# Minimum-System.net
KiCad netlist of a schematic drawn in EAGLE
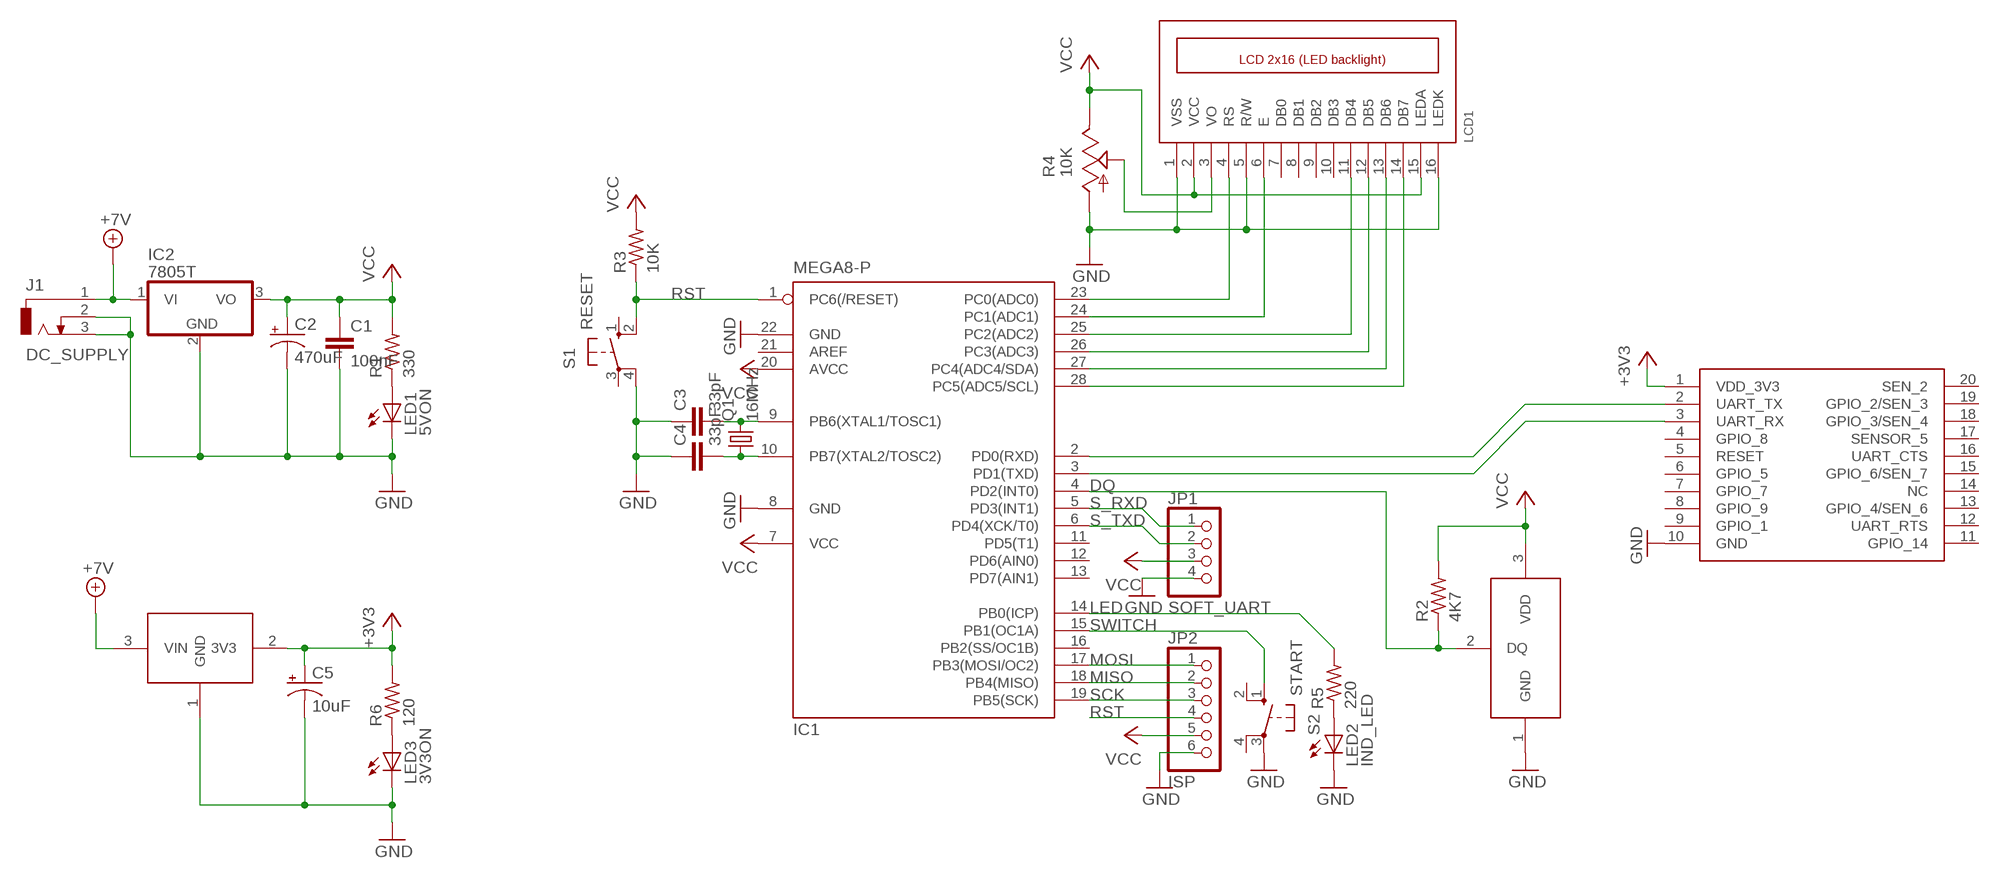
[diagram p0: schematic, sheet 1]

(export (version "E")
  (design (tool "Eeschema 10.0.6"))
  (components
    (comp (ref "C1")
      (value "100nF")
      (footprint "eagle-import:C025-024X044")
      (libsource (lib "eagle-import") (part "C-EU025-024X044"))
    )
    (comp (ref "C2")
      (value "470uF")
      (footprint "eagle-import:E2,5-7")
      (libsource (lib "eagle-import") (part "CPOL-USE2.5-7"))
    )
    (comp (ref "C3")
      (value "33pF")
      (footprint "eagle-import:C025-024X044")
      (libsource (lib "eagle-import") (part "C-EU025-024X044"))
    )
    (comp (ref "C4")
      (value "33pF")
      (footprint "eagle-import:C025-024X044")
      (libsource (lib "eagle-import") (part "C-EU025-024X044"))
    )
    (comp (ref "C5")
      (value "10uF")
      (footprint "eagle-import:E2,5-7")
      (libsource (lib "eagle-import") (part "CPOL-USE2.5-7"))
    )
    (comp (ref "IC1")
      (value "MEGA8-P")
      (footprint "eagle-import:DIL28-3")
      (libsource (lib "eagle-import") (part "MEGA8-P"))
    )
    (comp (ref "IC2")
      (value "7805T")
      (footprint "eagle-import:TO220H")
      (libsource (lib "eagle-import") (part "78T05"))
    )
    (comp (ref "J1")
      (value "DC_SUPPLY")
      (footprint "eagle-import:DCJ0202")
      (libsource (lib "eagle-import") (part "DCJ0202"))
    )
    (comp (ref "JP1")
      (value "SOFT_UART")
      (footprint "eagle-import:1X04")
      (libsource (lib "eagle-import") (part "PINHD-1X4"))
    )
    (comp (ref "JP2")
      (value "ISP")
      (footprint "eagle-import:1X06")
      (libsource (lib "eagle-import") (part "PINHD-1X6"))
    )
    (comp (ref "LCD1")
      (value "LCD_2X16")
      (footprint "eagle-import:HY-1602F")
      (libsource (lib "eagle-import") (part "LCD_2X16_SIL"))
    )
    (comp (ref "LED1")
      (value "5VON")
      (footprint "eagle-import:LED3MM")
      (libsource (lib "eagle-import") (part "LED3MM"))
    )
    (comp (ref "LED2")
      (value "IND_LED")
      (footprint "eagle-import:LED3MM")
      (libsource (lib "eagle-import") (part "LED3MM"))
    )
    (comp (ref "LED3")
      (value "3V3ON")
      (footprint "eagle-import:LED3MM")
      (libsource (lib "eagle-import") (part "LED3MM"))
    )
    (comp (ref "Q1")
      (value "16MHz")
      (footprint "eagle-import:HC49_S")
      (libsource (lib "eagle-import") (part "CRYSTALHC49S"))
    )
    (comp (ref "R1")
      (value "330")
      (footprint "eagle-import:0207_10")
      (libsource (lib "eagle-import") (part "R-US_0207/10"))
    )
    (comp (ref "R2")
      (value "4K7")
      (footprint "eagle-import:0207_10")
      (libsource (lib "eagle-import") (part "R-US_0207/10"))
    )
    (comp (ref "R3")
      (value "10K")
      (footprint "eagle-import:0207_10")
      (libsource (lib "eagle-import") (part "R-US_0207/10"))
    )
    (comp (ref "R4")
      (value "10K")
      (footprint "eagle-import:CA6V")
      (libsource (lib "eagle-import") (part "TRIM_US-CA6V"))
    )
    (comp (ref "R5")
      (value "220")
      (footprint "eagle-import:0207_10")
      (libsource (lib "eagle-import") (part "R-US_0207/10"))
    )
    (comp (ref "R6")
      (value "120")
      (footprint "eagle-import:0207_10")
      (libsource (lib "eagle-import") (part "R-US_0207/10"))
    )
    (comp (ref "S1")
      (value "RESET")
      (footprint "eagle-import:B3F-10XX")
      (fields (field (name "MPN") "B3F-1000"))
      (libsource (lib "eagle-import") (part "10-XX"))
    )
    (comp (ref "S2")
      (value "START")
      (footprint "eagle-import:B3F-10XX")
      (fields (field (name "MPN") "B3F-1000"))
      (libsource (lib "eagle-import") (part "10-XX"))
    )
    (comp (ref "U1")
      (value "DS1820")
      (footprint "eagle-import:TO92")
      (libsource (lib "eagle-import") (part "DS1820"))
    )
    (comp (ref "U2")
      (value "LD1117V33")
      (footprint "eagle-import:TO220")
      (libsource (lib "eagle-import") (part "LD1117V33"))
    )
    (comp (ref "U3")
      (value "WIFLY")
      (footprint "eagle-import:WIFLY_SOCKET")
      (libsource (lib "eagle-import") (part "WIFLY"))
    )
  )
  (nets
    (net (code "1") (name "+3V3") (class "Default")
      (node (ref "C5") (pin "+") (pinfunction "+_+") (pintype "passive"))
      (node (ref "R6") (pin "2") (pinfunction "2_2") (pintype "passive"))
      (node (ref "U2") (pin "2") (pinfunction "3V3_2") (pintype "bidirectional"))
      (node (ref "U3") (pin "1") (pinfunction "VDD_3V3_1") (pintype "power_in"))
    )
    (net (code "2") (name "+7V") (class "Default")
      (node (ref "IC2") (pin "1") (pinfunction "VI_1") (pintype "input"))
      (node (ref "J1") (pin "1") (pinfunction "1_1") (pintype "passive"))
      (node (ref "U2") (pin "3") (pinfunction "VIN_3") (pintype "input"))
    )
    (net (code "3") (name "/DQ") (class "Default")
      (node (ref "IC1") (pin "4") (pinfunction "PD2(INT0)_4") (pintype "bidirectional"))
      (node (ref "R2") (pin "1") (pinfunction "1_1") (pintype "passive"))
      (node (ref "U1") (pin "2") (pinfunction "DQ_2") (pintype "bidirectional"))
    )
    (net (code "4") (name "/LED") (class "Default")
      (node (ref "IC1") (pin "14") (pinfunction "PB0(ICP)_14") (pintype "bidirectional"))
      (node (ref "R5") (pin "2") (pinfunction "2_2") (pintype "passive"))
    )
    (net (code "5") (name "/MISO") (class "Default")
      (node (ref "IC1") (pin "18") (pinfunction "PB4(MISO)_18") (pintype "bidirectional"))
      (node (ref "JP2") (pin "2") (pinfunction "2_2") (pintype "passive"))
    )
    (net (code "6") (name "/MOSI") (class "Default")
      (node (ref "IC1") (pin "17") (pinfunction "PB3(MOSI/OC2)_17") (pintype "bidirectional"))
      (node (ref "JP2") (pin "1") (pinfunction "1_1") (pintype "passive"))
    )
    (net (code "7") (name "/RST") (class "Default")
      (node (ref "IC1") (pin "1") (pinfunction "PC6(/RESET)_1") (pintype "bidirectional"))
      (node (ref "JP2") (pin "4") (pinfunction "4_4") (pintype "passive"))
      (node (ref "R3") (pin "1") (pinfunction "1_1") (pintype "passive"))
      (node (ref "S1") (pin "2") (pinfunction "S1_2") (pintype "passive"))
    )
    (net (code "8") (name "/SCK") (class "Default")
      (node (ref "IC1") (pin "19") (pinfunction "PB5(SCK)_19") (pintype "bidirectional"))
      (node (ref "JP2") (pin "3") (pinfunction "3_3") (pintype "passive"))
    )
    (net (code "9") (name "/SWITCH") (class "Default")
      (node (ref "IC1") (pin "15") (pinfunction "PB1(OC1A)_15") (pintype "bidirectional"))
      (node (ref "S2") (pin "1") (pinfunction "S_1") (pintype "passive"))
    )
    (net (code "10") (name "/S_RXD") (class "Default")
      (node (ref "IC1") (pin "5") (pinfunction "PD3(INT1)_5") (pintype "bidirectional"))
      (node (ref "JP1") (pin "1") (pinfunction "1_1") (pintype "passive"))
    )
    (net (code "11") (name "/S_TXD") (class "Default")
      (node (ref "IC1") (pin "6") (pinfunction "PD4(XCK/T0)_6") (pintype "bidirectional"))
      (node (ref "JP1") (pin "2") (pinfunction "2_2") (pintype "passive"))
    )
    (net (code "12") (name "GND") (class "Default")
      (node (ref "C1") (pin "2") (pinfunction "2_2") (pintype "passive"))
      (node (ref "C2") (pin "-") (pinfunction "-_-") (pintype "passive"))
      (node (ref "C3") (pin "1") (pinfunction "1_1") (pintype "passive"))
      (node (ref "C4") (pin "1") (pinfunction "1_1") (pintype "passive"))
      (node (ref "C5") (pin "-") (pinfunction "-_-") (pintype "passive"))
      (node (ref "IC1") (pin "22") (pinfunction "GND_22") (pintype "power_in"))
      (node (ref "IC1") (pin "8") (pinfunction "GND_8") (pintype "power_in"))
      (node (ref "IC2") (pin "2") (pinfunction "GND_2") (pintype "passive"))
      (node (ref "J1") (pin "2") (pinfunction "2_2") (pintype "passive"))
      (node (ref "J1") (pin "3") (pinfunction "3_3") (pintype "passive"))
      (node (ref "JP1") (pin "4") (pinfunction "4_4") (pintype "passive"))
      (node (ref "JP2") (pin "6") (pinfunction "6_6") (pintype "passive"))
      (node (ref "LCD1") (pin "1") (pinfunction "VSS_1") (pintype "power_in"))
      (node (ref "LCD1") (pin "16") (pinfunction "LEDK_16") (pintype "passive"))
      (node (ref "LCD1") (pin "5") (pinfunction "R/W_5") (pintype "input"))
      (node (ref "LED1") (pin "K") (pinfunction "C_K") (pintype "passive"))
      (node (ref "LED2") (pin "K") (pinfunction "C_K") (pintype "passive"))
      (node (ref "LED3") (pin "K") (pinfunction "C_K") (pintype "passive"))
      (node (ref "R4") (pin "A") (pinfunction "A_A") (pintype "passive"))
      (node (ref "S1") (pin "4") (pinfunction "P1_4") (pintype "passive"))
      (node (ref "S2") (pin "3") (pinfunction "P_3") (pintype "passive"))
      (node (ref "U1") (pin "1") (pinfunction "GND_1") (pintype "power_in"))
      (node (ref "U2") (pin "1") (pinfunction "GND_1") (pintype "power_in"))
      (node (ref "U3") (pin "10") (pinfunction "GND_10") (pintype "power_in"))
    )
    (net (code "13") (name "Net-(IC1-PB6(XTAL1{slash}TOSC1))") (class "Default")
      (node (ref "C3") (pin "2") (pinfunction "2_2") (pintype "passive"))
      (node (ref "IC1") (pin "9") (pinfunction "PB6(XTAL1/TOSC1)_9") (pintype "bidirectional"))
      (node (ref "Q1") (pin "2") (pinfunction "2_2") (pintype "passive"))
    )
    (net (code "14") (name "Net-(IC1-PB7(XTAL2{slash}TOSC2))") (class "Default")
      (node (ref "C4") (pin "2") (pinfunction "2_2") (pintype "passive"))
      (node (ref "IC1") (pin "10") (pinfunction "PB7(XTAL2/TOSC2)_10") (pintype "bidirectional"))
      (node (ref "Q1") (pin "1") (pinfunction "1_1") (pintype "passive"))
    )
    (net (code "15") (name "Net-(IC1-PC0(ADC0))") (class "Default")
      (node (ref "IC1") (pin "23") (pinfunction "PC0(ADC0)_23") (pintype "bidirectional"))
      (node (ref "LCD1") (pin "4") (pinfunction "RS_4") (pintype "input"))
    )
    (net (code "16") (name "Net-(IC1-PC1(ADC1))") (class "Default")
      (node (ref "IC1") (pin "24") (pinfunction "PC1(ADC1)_24") (pintype "bidirectional"))
      (node (ref "LCD1") (pin "6") (pinfunction "E_6") (pintype "input"))
    )
    (net (code "17") (name "Net-(IC1-PC2(ADC2))") (class "Default")
      (node (ref "IC1") (pin "25") (pinfunction "PC2(ADC2)_25") (pintype "bidirectional"))
      (node (ref "LCD1") (pin "11") (pinfunction "DB4_11") (pintype "bidirectional"))
    )
    (net (code "18") (name "Net-(IC1-PC3(ADC3))") (class "Default")
      (node (ref "IC1") (pin "26") (pinfunction "PC3(ADC3)_26") (pintype "bidirectional"))
      (node (ref "LCD1") (pin "12") (pinfunction "DB5_12") (pintype "bidirectional"))
    )
    (net (code "19") (name "Net-(IC1-PC4(ADC4{slash}SDA))") (class "Default")
      (node (ref "IC1") (pin "27") (pinfunction "PC4(ADC4/SDA)_27") (pintype "bidirectional"))
      (node (ref "LCD1") (pin "13") (pinfunction "DB6_13") (pintype "bidirectional"))
    )
    (net (code "20") (name "Net-(IC1-PC5(ADC5{slash}SCL))") (class "Default")
      (node (ref "IC1") (pin "28") (pinfunction "PC5(ADC5/SCL)_28") (pintype "bidirectional"))
      (node (ref "LCD1") (pin "14") (pinfunction "DB7_14") (pintype "bidirectional"))
    )
    (net (code "21") (name "Net-(IC1-PD0(RXD))") (class "Default")
      (node (ref "IC1") (pin "2") (pinfunction "PD0(RXD)_2") (pintype "bidirectional"))
      (node (ref "U3") (pin "2") (pinfunction "UART_TX_2") (pintype "bidirectional"))
    )
    (net (code "22") (name "Net-(IC1-PD1(TXD))") (class "Default")
      (node (ref "IC1") (pin "3") (pinfunction "PD1(TXD)_3") (pintype "bidirectional"))
      (node (ref "U3") (pin "3") (pinfunction "UART_RX_3") (pintype "bidirectional"))
    )
    (net (code "23") (name "Net-(LCD1-VO)") (class "Default")
      (node (ref "LCD1") (pin "3") (pinfunction "VO_3") (pintype "input"))
      (node (ref "R4") (pin "S") (pinfunction "S_S") (pintype "passive"))
    )
    (net (code "24") (name "Net-(LED1-PadA)") (class "Default")
      (node (ref "LED1") (pin "A") (pinfunction "A_A") (pintype "passive"))
      (node (ref "R1") (pin "1") (pinfunction "1_1") (pintype "passive"))
    )
    (net (code "25") (name "Net-(LED2-PadA)") (class "Default")
      (node (ref "LED2") (pin "A") (pinfunction "A_A") (pintype "passive"))
      (node (ref "R5") (pin "1") (pinfunction "1_1") (pintype "passive"))
    )
    (net (code "26") (name "Net-(LED3-PadA)") (class "Default")
      (node (ref "LED3") (pin "A") (pinfunction "A_A") (pintype "passive"))
      (node (ref "R6") (pin "1") (pinfunction "1_1") (pintype "passive"))
    )
    (net (code "27") (name "VCC") (class "Default")
      (node (ref "C1") (pin "1") (pinfunction "1_1") (pintype "passive"))
      (node (ref "C2") (pin "+") (pinfunction "+_+") (pintype "passive"))
      (node (ref "IC1") (pin "20") (pinfunction "AVCC_20") (pintype "power_in"))
      (node (ref "IC1") (pin "7") (pinfunction "VCC_7") (pintype "power_in"))
      (node (ref "IC2") (pin "3") (pinfunction "VO_3") (pintype "passive"))
      (node (ref "JP1") (pin "3") (pinfunction "3_3") (pintype "passive"))
      (node (ref "JP2") (pin "5") (pinfunction "5_5") (pintype "passive"))
      (node (ref "LCD1") (pin "15") (pinfunction "LEDA_15") (pintype "passive"))
      (node (ref "LCD1") (pin "2") (pinfunction "VCC_2") (pintype "power_in"))
      (node (ref "R1") (pin "2") (pinfunction "2_2") (pintype "passive"))
      (node (ref "R2") (pin "2") (pinfunction "2_2") (pintype "passive"))
      (node (ref "R3") (pin "2") (pinfunction "2_2") (pintype "passive"))
      (node (ref "R4") (pin "E") (pinfunction "E_E") (pintype "passive"))
      (node (ref "U1") (pin "3") (pinfunction "VDD_3") (pintype "power_in"))
    )
    (net (code "28") (name "unconnected-(IC1-AREF-Pad21)") (class "Default")
      (node (ref "IC1") (pin "21") (pinfunction "AREF_21") (pintype "passive"))
    )
    (net (code "29") (name "unconnected-(IC1-PB2(SS{slash}OC1B)-Pad16)") (class "Default")
      (node (ref "IC1") (pin "16") (pinfunction "PB2(SS/OC1B)_16") (pintype "bidirectional"))
    )
    (net (code "30") (name "unconnected-(IC1-PD5(T1)-Pad11)") (class "Default")
      (node (ref "IC1") (pin "11") (pinfunction "PD5(T1)_11") (pintype "bidirectional"))
    )
    (net (code "31") (name "unconnected-(IC1-PD6(AIN0)-Pad12)") (class "Default")
      (node (ref "IC1") (pin "12") (pinfunction "PD6(AIN0)_12") (pintype "bidirectional"))
    )
    (net (code "32") (name "unconnected-(IC1-PD7(AIN1)-Pad13)") (class "Default")
      (node (ref "IC1") (pin "13") (pinfunction "PD7(AIN1)_13") (pintype "bidirectional"))
    )
    (net (code "33") (name "unconnected-(LCD1-DB0-Pad7)") (class "Default")
      (node (ref "LCD1") (pin "7") (pinfunction "DB0_7") (pintype "bidirectional"))
    )
    (net (code "34") (name "unconnected-(LCD1-DB1-Pad8)") (class "Default")
      (node (ref "LCD1") (pin "8") (pinfunction "DB1_8") (pintype "bidirectional"))
    )
    (net (code "35") (name "unconnected-(LCD1-DB2-Pad9)") (class "Default")
      (node (ref "LCD1") (pin "9") (pinfunction "DB2_9") (pintype "bidirectional"))
    )
    (net (code "36") (name "unconnected-(LCD1-DB3-Pad10)") (class "Default")
      (node (ref "LCD1") (pin "10") (pinfunction "DB3_10") (pintype "bidirectional"))
    )
    (net (code "37") (name "unconnected-(S1-P-Pad3)") (class "Default")
      (node (ref "S1") (pin "3") (pinfunction "P_3") (pintype "passive"))
    )
    (net (code "38") (name "unconnected-(S1-S-Pad1)") (class "Default")
      (node (ref "S1") (pin "1") (pinfunction "S_1") (pintype "passive"))
    )
    (net (code "39") (name "unconnected-(S2-P1-Pad4)") (class "Default")
      (node (ref "S2") (pin "4") (pinfunction "P1_4") (pintype "passive"))
    )
    (net (code "40") (name "unconnected-(S2-S1-Pad2)") (class "Default")
      (node (ref "S2") (pin "2") (pinfunction "S1_2") (pintype "passive"))
    )
    (net (code "41") (name "unconnected-(U3-GPIO_1-Pad9)") (class "Default")
      (node (ref "U3") (pin "9") (pinfunction "GPIO_1_9") (pintype "bidirectional"))
    )
    (net (code "42") (name "unconnected-(U3-GPIO_2{slash}SEN_3-Pad19)") (class "Default")
      (node (ref "U3") (pin "19") (pinfunction "GPIO_2/SEN_3_19") (pintype "bidirectional"))
    )
    (net (code "43") (name "unconnected-(U3-GPIO_3{slash}SEN_4-Pad18)") (class "Default")
      (node (ref "U3") (pin "18") (pinfunction "GPIO_3/SEN_4_18") (pintype "bidirectional"))
    )
    (net (code "44") (name "unconnected-(U3-GPIO_4{slash}SEN_6-Pad13)") (class "Default")
      (node (ref "U3") (pin "13") (pinfunction "GPIO_4/SEN_6_13") (pintype "bidirectional"))
    )
    (net (code "45") (name "unconnected-(U3-GPIO_5-Pad6)") (class "Default")
      (node (ref "U3") (pin "6") (pinfunction "GPIO_5_6") (pintype "bidirectional"))
    )
    (net (code "46") (name "unconnected-(U3-GPIO_6{slash}SEN_7-Pad15)") (class "Default")
      (node (ref "U3") (pin "15") (pinfunction "GPIO_6/SEN_7_15") (pintype "bidirectional"))
    )
    (net (code "47") (name "unconnected-(U3-GPIO_7-Pad7)") (class "Default")
      (node (ref "U3") (pin "7") (pinfunction "GPIO_7_7") (pintype "bidirectional"))
    )
    (net (code "48") (name "unconnected-(U3-GPIO_8-Pad4)") (class "Default")
      (node (ref "U3") (pin "4") (pinfunction "GPIO_8_4") (pintype "bidirectional"))
    )
    (net (code "49") (name "unconnected-(U3-GPIO_9-Pad8)") (class "Default")
      (node (ref "U3") (pin "8") (pinfunction "GPIO_9_8") (pintype "bidirectional"))
    )
    (net (code "50") (name "unconnected-(U3-GPIO_14-Pad11)") (class "Default")
      (node (ref "U3") (pin "11") (pinfunction "GPIO_14_11") (pintype "bidirectional"))
    )
    (net (code "51") (name "unconnected-(U3-NC-Pad14)") (class "Default")
      (node (ref "U3") (pin "14") (pinfunction "NC_14") (pintype "bidirectional"))
    )
    (net (code "52") (name "unconnected-(U3-RESET-Pad5)") (class "Default")
      (node (ref "U3") (pin "5") (pinfunction "RESET_5") (pintype "bidirectional"))
    )
    (net (code "53") (name "unconnected-(U3-SENSOR_5-Pad17)") (class "Default")
      (node (ref "U3") (pin "17") (pinfunction "SENSOR_5_17") (pintype "bidirectional"))
    )
    (net (code "54") (name "unconnected-(U3-SEN_2-Pad20)") (class "Default")
      (node (ref "U3") (pin "20") (pinfunction "SEN_2_20") (pintype "bidirectional"))
    )
    (net (code "55") (name "unconnected-(U3-UART_CTS-Pad16)") (class "Default")
      (node (ref "U3") (pin "16") (pinfunction "UART_CTS_16") (pintype "bidirectional"))
    )
    (net (code "56") (name "unconnected-(U3-UART_RTS-Pad12)") (class "Default")
      (node (ref "U3") (pin "12") (pinfunction "UART_RTS_12") (pintype "bidirectional"))
    )
  )
)
